# LCD.net
KiCad netlist of a schematic drawn in Altium Designer
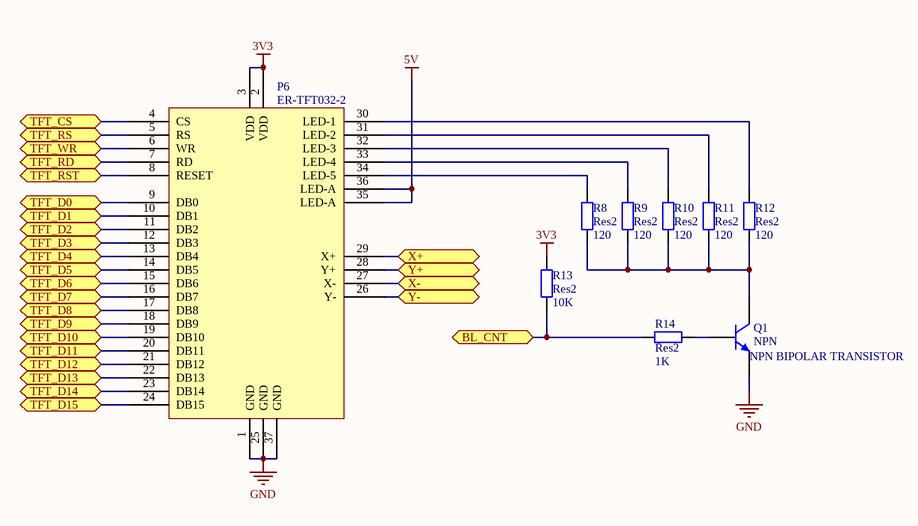
[diagram p0: LCD.SchDoc]

(export (version "E")
  (design (tool "Eeschema 10.0.6"))
  (components
    (comp (ref "P6")
      (value "ER-TFT032-2")
      (footprint "ER-TFT032-2")
      (description "3.2\" TFT LCD module with touch panel")
      (libsource (lib "BrewBit") (part "ER-TFT032-2"))
    )
    (comp (ref "Q1")
      (value "NPN")
      (footprint "SOT23_M")
      (description "NPN Bipolar Transistor")
      (fields (field (name "ALTIUM_VALUE") "NPN BIPOLAR TRANSISTOR"))
      (libsource (lib "Miscellaneous Devices") (part "NPN"))
    )
    (comp (ref "R8")
      (value "Res2")
      (footprint "0603")
      (description "Resistor")
      (fields (field (name "ALTIUM_VALUE") "120"))
      (libsource (lib "Miscellaneous Devices") (part "Res2"))
    )
    (comp (ref "R9")
      (value "Res2")
      (footprint "0603")
      (description "Resistor")
      (fields (field (name "ALTIUM_VALUE") "120"))
      (libsource (lib "Miscellaneous Devices") (part "Res2"))
    )
    (comp (ref "R10")
      (value "Res2")
      (footprint "0603")
      (description "Resistor")
      (fields (field (name "ALTIUM_VALUE") "120"))
      (libsource (lib "Miscellaneous Devices") (part "Res2"))
    )
    (comp (ref "R11")
      (value "Res2")
      (footprint "0603")
      (description "Resistor")
      (fields (field (name "ALTIUM_VALUE") "120"))
      (libsource (lib "Miscellaneous Devices") (part "Res2"))
    )
    (comp (ref "R12")
      (value "Res2")
      (footprint "0603")
      (description "Resistor")
      (fields (field (name "ALTIUM_VALUE") "120"))
      (libsource (lib "Miscellaneous Devices") (part "Res2"))
    )
    (comp (ref "R13")
      (value "Res2")
      (footprint "0603")
      (description "Resistor")
      (fields (field (name "ALTIUM_VALUE") "10K"))
      (libsource (lib "Miscellaneous Devices") (part "Res2"))
    )
    (comp (ref "R14")
      (value "Res2")
      (footprint "0603")
      (description "Resistor")
      (fields (field (name "ALTIUM_VALUE") "1K"))
      (libsource (lib "") (part "Res2_1"))
    )
  )
  (nets
    (net (code "1") (name "/BL_CNT") (class "Default")
      (node (ref "R13") (pin "1") (pinfunction "1_1") (pintype "passive"))
      (node (ref "R14") (pin "2") (pinfunction "2_2") (pintype "passive"))
    )
    (net (code "2") (name "/TFT_CS") (class "Default")
      (node (ref "P6") (pin "4") (pinfunction "CS_4") (pintype "passive"))
    )
    (net (code "3") (name "/TFT_D0") (class "Default")
      (node (ref "P6") (pin "9") (pinfunction "DB0_9") (pintype "passive"))
    )
    (net (code "4") (name "/TFT_D1") (class "Default")
      (node (ref "P6") (pin "10") (pinfunction "DB1_10") (pintype "passive"))
    )
    (net (code "5") (name "/TFT_D2") (class "Default")
      (node (ref "P6") (pin "11") (pinfunction "DB2_11") (pintype "passive"))
    )
    (net (code "6") (name "/TFT_D3") (class "Default")
      (node (ref "P6") (pin "12") (pinfunction "DB3_12") (pintype "passive"))
    )
    (net (code "7") (name "/TFT_D4") (class "Default")
      (node (ref "P6") (pin "13") (pinfunction "DB4_13") (pintype "passive"))
    )
    (net (code "8") (name "/TFT_D5") (class "Default")
      (node (ref "P6") (pin "14") (pinfunction "DB5_14") (pintype "passive"))
    )
    (net (code "9") (name "/TFT_D6") (class "Default")
      (node (ref "P6") (pin "15") (pinfunction "DB6_15") (pintype "passive"))
    )
    (net (code "10") (name "/TFT_D7") (class "Default")
      (node (ref "P6") (pin "16") (pinfunction "DB7_16") (pintype "passive"))
    )
    (net (code "11") (name "/TFT_D8") (class "Default")
      (node (ref "P6") (pin "17") (pinfunction "DB8_17") (pintype "passive"))
    )
    (net (code "12") (name "/TFT_D9") (class "Default")
      (node (ref "P6") (pin "18") (pinfunction "DB9_18") (pintype "passive"))
    )
    (net (code "13") (name "/TFT_D10") (class "Default")
      (node (ref "P6") (pin "19") (pinfunction "DB10_19") (pintype "passive"))
    )
    (net (code "14") (name "/TFT_D11") (class "Default")
      (node (ref "P6") (pin "20") (pinfunction "DB11_20") (pintype "passive"))
    )
    (net (code "15") (name "/TFT_D12") (class "Default")
      (node (ref "P6") (pin "21") (pinfunction "DB12_21") (pintype "passive"))
    )
    (net (code "16") (name "/TFT_D13") (class "Default")
      (node (ref "P6") (pin "22") (pinfunction "DB13_22") (pintype "passive"))
    )
    (net (code "17") (name "/TFT_D14") (class "Default")
      (node (ref "P6") (pin "23") (pinfunction "DB14_23") (pintype "passive"))
    )
    (net (code "18") (name "/TFT_D15") (class "Default")
      (node (ref "P6") (pin "24") (pinfunction "DB15_24") (pintype "passive"))
    )
    (net (code "19") (name "/TFT_RD") (class "Default")
      (node (ref "P6") (pin "7") (pinfunction "RD_7") (pintype "passive"))
    )
    (net (code "20") (name "/TFT_RS") (class "Default")
      (node (ref "P6") (pin "5") (pinfunction "RS_5") (pintype "passive"))
    )
    (net (code "21") (name "/TFT_RST") (class "Default")
      (node (ref "P6") (pin "8") (pinfunction "RESET_8") (pintype "passive"))
    )
    (net (code "22") (name "/TFT_WR") (class "Default")
      (node (ref "P6") (pin "6") (pinfunction "WR_6") (pintype "passive"))
    )
    (net (code "23") (name "/X+") (class "Default")
      (node (ref "P6") (pin "29") (pinfunction "X+_29") (pintype "passive"))
    )
    (net (code "24") (name "/X-") (class "Default")
      (node (ref "P6") (pin "27") (pinfunction "X-_27") (pintype "passive"))
    )
    (net (code "25") (name "/Y+") (class "Default")
      (node (ref "P6") (pin "28") (pinfunction "Y+_28") (pintype "passive"))
    )
    (net (code "26") (name "/Y-") (class "Default")
      (node (ref "P6") (pin "26") (pinfunction "Y-_26") (pintype "passive"))
    )
    (net (code "27") (name "3V3") (class "Default")
      (node (ref "P6") (pin "2") (pinfunction "VDD_2") (pintype "passive"))
      (node (ref "P6") (pin "3") (pinfunction "VDD_3") (pintype "passive"))
      (node (ref "R13") (pin "2") (pinfunction "2_2") (pintype "passive"))
    )
    (net (code "28") (name "5V") (class "Default")
      (node (ref "P6") (pin "35") (pinfunction "LED-A_35") (pintype "passive"))
      (node (ref "P6") (pin "36") (pinfunction "LED-A_36") (pintype "passive"))
    )
    (net (code "29") (name "GND") (class "Default")
      (node (ref "P6") (pin "1") (pinfunction "GND_1") (pintype "passive"))
      (node (ref "P6") (pin "25") (pinfunction "GND_25") (pintype "passive"))
      (node (ref "P6") (pin "37") (pinfunction "GND_37") (pintype "passive"))
      (node (ref "Q1") (pin "3") (pinfunction "E_3") (pintype "passive"))
    )
    (net (code "30") (name "Net-(P6-LED-1)") (class "Default")
      (node (ref "P6") (pin "30") (pinfunction "LED-1_30") (pintype "passive"))
      (node (ref "R12") (pin "2") (pinfunction "2_2") (pintype "passive"))
    )
    (net (code "31") (name "Net-(P6-LED-2)") (class "Default")
      (node (ref "P6") (pin "31") (pinfunction "LED-2_31") (pintype "passive"))
      (node (ref "R11") (pin "2") (pinfunction "2_2") (pintype "passive"))
    )
    (net (code "32") (name "Net-(P6-LED-3)") (class "Default")
      (node (ref "P6") (pin "32") (pinfunction "LED-3_32") (pintype "passive"))
      (node (ref "R10") (pin "2") (pinfunction "2_2") (pintype "passive"))
    )
    (net (code "33") (name "Net-(P6-LED-4)") (class "Default")
      (node (ref "P6") (pin "33") (pinfunction "LED-4_33") (pintype "passive"))
      (node (ref "R9") (pin "2") (pinfunction "2_2") (pintype "passive"))
    )
    (net (code "34") (name "Net-(P6-LED-5)") (class "Default")
      (node (ref "P6") (pin "34") (pinfunction "LED-5_34") (pintype "passive"))
      (node (ref "R8") (pin "2") (pinfunction "2_2") (pintype "passive"))
    )
    (net (code "35") (name "Net-(Q1-B)") (class "Default")
      (node (ref "Q1") (pin "2") (pinfunction "B_2") (pintype "passive"))
      (node (ref "R14") (pin "1") (pinfunction "1_1") (pintype "passive"))
    )
    (net (code "36") (name "Net-(Q1-C)") (class "Default")
      (node (ref "Q1") (pin "1") (pinfunction "C_1") (pintype "passive"))
      (node (ref "R10") (pin "1") (pinfunction "1_1") (pintype "passive"))
      (node (ref "R11") (pin "1") (pinfunction "1_1") (pintype "passive"))
      (node (ref "R12") (pin "1") (pinfunction "1_1") (pintype "passive"))
      (node (ref "R8") (pin "1") (pinfunction "1_1") (pintype "passive"))
      (node (ref "R9") (pin "1") (pinfunction "1_1") (pintype "passive"))
    )
  )
)
